# 03_RS485.net
KiCad netlist of a schematic drawn in Altium Designer
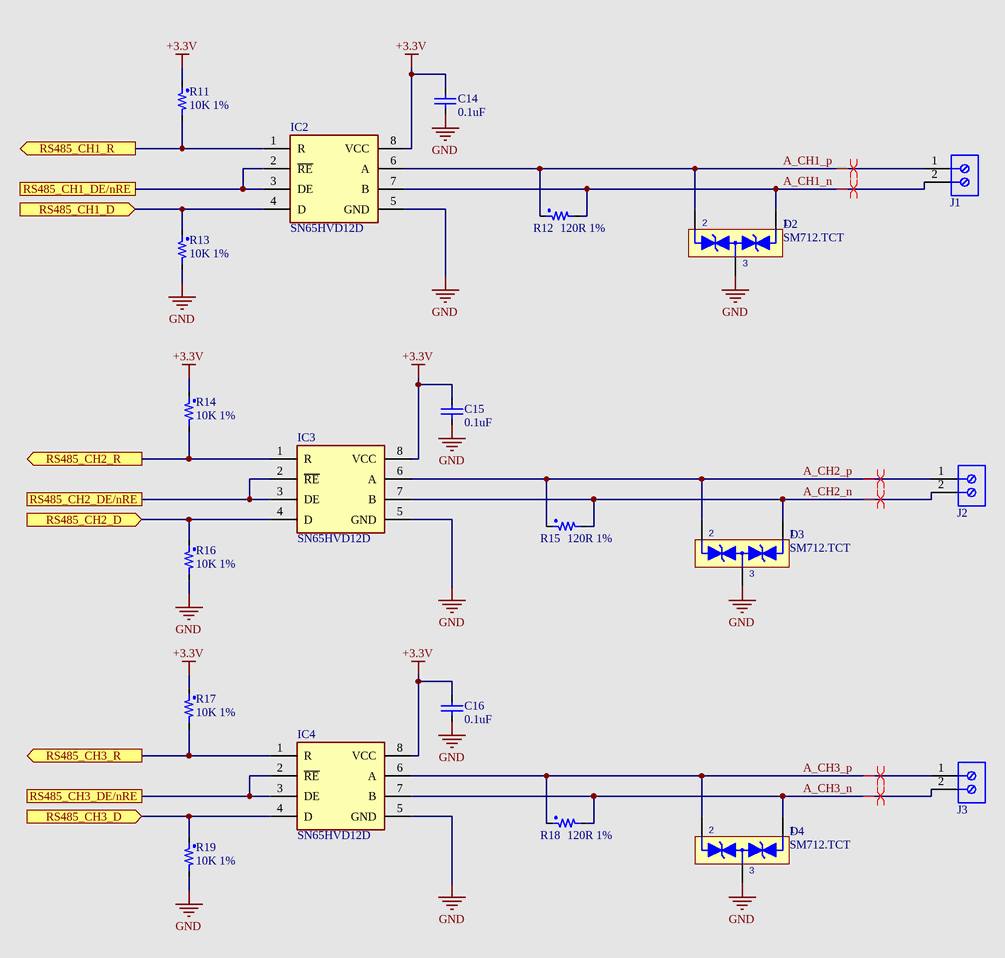
[diagram p0: 03_RS485.SchDoc]

(export (version "E")
  (design (tool "Eeschema 10.0.6"))
  (components
    (comp (ref "C14")
      (value "0.1uF")
      (footprint "Capacitor:C0603 (1608 metric)")
      (description "Multilayer Ceramic Capacitors MLCC - SMD/SMT 0.1uF 50V X7R +/-10% 0603")
      (fields (field (name "MFR PART NUMBER") "CC0603KRX7R9BB104") (field (name "MFR") "Yageo"))
      (libsource (lib "CeramicCapacitor") (part "CC0603KRX7R9BB104"))
    )
    (comp (ref "C15")
      (value "0.1uF")
      (footprint "Capacitor:C0603 (1608 metric)")
      (description "Multilayer Ceramic Capacitors MLCC - SMD/SMT 0.1uF 50V X7R +/-10% 0603")
      (fields (field (name "MFR PART NUMBER") "CC0603KRX7R9BB104") (field (name "MFR") "Yageo"))
      (libsource (lib "CeramicCapacitor") (part "CC0603KRX7R9BB104"))
    )
    (comp (ref "C16")
      (value "0.1uF")
      (footprint "Capacitor:C0603 (1608 metric)")
      (description "Multilayer Ceramic Capacitors MLCC - SMD/SMT 0.1uF 50V X7R +/-10% 0603")
      (fields (field (name "MFR PART NUMBER") "CC0603KRX7R9BB104") (field (name "MFR") "Yageo"))
      (libsource (lib "CeramicCapacitor") (part "CC0603KRX7R9BB104"))
    )
    (comp (ref "D2")
      (value "SM712.TCT")
      (footprint "SM712")
      (description "ESD Suppressors / TVS Diodes 400W ASYMMETRICAL TVS 7V,12V")
      (fields (field (name "MFR") "SEMTECH"))
      (libsource (lib "ESD Suppressors and TVS Diodes") (part "SM712.TCT"))
    )
    (comp (ref "D3")
      (value "SM712.TCT")
      (footprint "SM712")
      (description "ESD Suppressors / TVS Diodes 400W ASYMMETRICAL TVS 7V,12V")
      (fields (field (name "MFR") "SEMTECH"))
      (libsource (lib "ESD Suppressors and TVS Diodes") (part "SM712.TCT"))
    )
    (comp (ref "D4")
      (value "SM712.TCT")
      (footprint "SM712")
      (description "ESD Suppressors / TVS Diodes 400W ASYMMETRICAL TVS 7V,12V")
      (fields (field (name "MFR") "SEMTECH"))
      (libsource (lib "ESD Suppressors and TVS Diodes") (part "SM712.TCT"))
    )
    (comp (ref "IC2")
      (value "SN65HVD12D")
      (footprint "SOIC8")
      (description "RS-485 Interface IC 3.3V Differential Transceivers")
      (fields (field (name "MFR") "Texas Instruments") (field (name "MFR PART NUMBER") "SN65HVD12DR"))
      (libsource (lib "Interface") (part "SN65HVD12D"))
    )
    (comp (ref "IC3")
      (value "SN65HVD12D")
      (footprint "SOIC8")
      (description "RS-485 Interface IC 3.3V Differential Transceivers")
      (fields (field (name "MFR") "Texas Instruments") (field (name "MFR PART NUMBER") "SN65HVD12DR"))
      (libsource (lib "Interface") (part "SN65HVD12D"))
    )
    (comp (ref "IC4")
      (value "SN65HVD12D")
      (footprint "SOIC8")
      (description "RS-485 Interface IC 3.3V Differential Transceivers")
      (fields (field (name "MFR") "Texas Instruments") (field (name "MFR PART NUMBER") "SN65HVD12DR"))
      (libsource (lib "Interface") (part "SN65HVD12D"))
    )
    (comp (ref "J1")
      (value "691103110002")
      (footprint "691103110002")
      (description "WR-TBL Series 1031 Horizontal Entry Modular, THT, pitch 3.5mm, 2p")
      (fields (field (name "MFR") "Wurth Elektronik"))
      (libsource (lib "Altium_WR-TBL (rev22b)") (part "691103110002"))
    )
    (comp (ref "J2")
      (value "691103110002")
      (footprint "691103110002")
      (description "WR-TBL Series 1031 Horizontal Entry Modular, THT, pitch 3.5mm, 2p")
      (fields (field (name "MFR") "Wurth Elektronik"))
      (libsource (lib "Altium_WR-TBL (rev22b)") (part "691103110002"))
    )
    (comp (ref "J3")
      (value "691103110002")
      (footprint "691103110002")
      (description "WR-TBL Series 1031 Horizontal Entry Modular, THT, pitch 3.5mm, 2p")
      (fields (field (name "MFR") "Wurth Elektronik"))
      (libsource (lib "Altium_WR-TBL (rev22b)") (part "691103110002"))
    )
    (comp (ref "R11")
      (value "10K 1%")
      (footprint "Resistor:R0603 (1608 Metric)")
      (description "Thick Film Resistors - SMD 10K OHM 1% Case 0603")
      (fields (field (name "MFR PART NUMBER") "RC0603FR-0710KL") (field (name "MFR") "Yageo"))
      (libsource (lib "ChipResistor") (part "RC0603FR-0710KL"))
    )
    (comp (ref "R12")
      (value "120R 1%")
      (footprint "Resistor:R0805 (2012 METRIC)")
      (description "Thick Film Resistors - SMD 120 OHM 1%")
      (fields (field (name "MFR PART NUMBER") "RC0805FR-07120RL") (field (name "MFR") "Yageo"))
      (libsource (lib "ChipResistor") (part "RC0805FR-07120RL"))
    )
    (comp (ref "R13")
      (value "10K 1%")
      (footprint "Resistor:R0603 (1608 Metric)")
      (description "Thick Film Resistors - SMD 10K OHM 1% Case 0603")
      (fields (field (name "MFR PART NUMBER") "RC0603FR-0710KL") (field (name "MFR") "Yageo"))
      (libsource (lib "ChipResistor") (part "RC0603FR-0710KL"))
    )
    (comp (ref "R14")
      (value "10K 1%")
      (footprint "Resistor:R0603 (1608 Metric)")
      (description "Thick Film Resistors - SMD 10K OHM 1% Case 0603")
      (fields (field (name "MFR PART NUMBER") "RC0603FR-0710KL") (field (name "MFR") "Yageo"))
      (libsource (lib "ChipResistor") (part "RC0603FR-0710KL"))
    )
    (comp (ref "R15")
      (value "120R 1%")
      (footprint "Resistor:R0805 (2012 METRIC)")
      (description "Thick Film Resistors - SMD 120 OHM 1%")
      (fields (field (name "MFR PART NUMBER") "RC0805FR-07120RL") (field (name "MFR") "Yageo"))
      (libsource (lib "ChipResistor") (part "RC0805FR-07120RL"))
    )
    (comp (ref "R16")
      (value "10K 1%")
      (footprint "Resistor:R0603 (1608 Metric)")
      (description "Thick Film Resistors - SMD 10K OHM 1% Case 0603")
      (fields (field (name "MFR PART NUMBER") "RC0603FR-0710KL") (field (name "MFR") "Yageo"))
      (libsource (lib "ChipResistor") (part "RC0603FR-0710KL"))
    )
    (comp (ref "R17")
      (value "10K 1%")
      (footprint "Resistor:R0603 (1608 Metric)")
      (description "Thick Film Resistors - SMD 10K OHM 1% Case 0603")
      (fields (field (name "MFR PART NUMBER") "RC0603FR-0710KL") (field (name "MFR") "Yageo"))
      (libsource (lib "ChipResistor") (part "RC0603FR-0710KL"))
    )
    (comp (ref "R18")
      (value "120R 1%")
      (footprint "Resistor:R0805 (2012 METRIC)")
      (description "Thick Film Resistors - SMD 120 OHM 1%")
      (fields (field (name "MFR PART NUMBER") "RC0805FR-07120RL") (field (name "MFR") "Yageo"))
      (libsource (lib "ChipResistor") (part "RC0805FR-07120RL"))
    )
    (comp (ref "R19")
      (value "10K 1%")
      (footprint "Resistor:R0603 (1608 Metric)")
      (description "Thick Film Resistors - SMD 10K OHM 1% Case 0603")
      (fields (field (name "MFR PART NUMBER") "RC0603FR-0710KL") (field (name "MFR") "Yageo"))
      (libsource (lib "ChipResistor") (part "RC0603FR-0710KL"))
    )
  )
  (nets
    (net (code "1") (name "+3.3V") (class "Default")
      (node (ref "C14") (pin "1") (pinfunction "1_1") (pintype "passive"))
      (node (ref "C15") (pin "1") (pinfunction "1_1") (pintype "passive"))
      (node (ref "C16") (pin "1") (pinfunction "1_1") (pintype "passive"))
      (node (ref "IC2") (pin "8") (pinfunction "VCC_8") (pintype "passive"))
      (node (ref "IC3") (pin "8") (pinfunction "VCC_8") (pintype "passive"))
      (node (ref "IC4") (pin "8") (pinfunction "VCC_8") (pintype "passive"))
      (node (ref "R11") (pin "1") (pinfunction "1_1") (pintype "passive"))
      (node (ref "R14") (pin "1") (pinfunction "1_1") (pintype "passive"))
      (node (ref "R17") (pin "1") (pinfunction "1_1") (pintype "passive"))
    )
    (net (code "2") (name "/A_CH1_n") (class "Default")
      (node (ref "D2") (pin "1") (pinfunction "I/O1_1") (pintype "passive"))
      (node (ref "IC2") (pin "7") (pinfunction "B_7") (pintype "passive"))
      (node (ref "J1") (pin "2") (pinfunction "2_2") (pintype "passive"))
      (node (ref "R12") (pin "2") (pinfunction "2_2") (pintype "passive"))
    )
    (net (code "3") (name "/A_CH1_p") (class "Default")
      (node (ref "D2") (pin "2") (pinfunction "I/O2_2") (pintype "passive"))
      (node (ref "IC2") (pin "6") (pinfunction "A_6") (pintype "passive"))
      (node (ref "J1") (pin "1") (pinfunction "1_1") (pintype "passive"))
      (node (ref "R12") (pin "1") (pinfunction "1_1") (pintype "passive"))
    )
    (net (code "4") (name "/A_CH2_n") (class "Default")
      (node (ref "D3") (pin "1") (pinfunction "I/O1_1") (pintype "passive"))
      (node (ref "IC3") (pin "7") (pinfunction "B_7") (pintype "passive"))
      (node (ref "J2") (pin "2") (pinfunction "2_2") (pintype "passive"))
      (node (ref "R15") (pin "2") (pinfunction "2_2") (pintype "passive"))
    )
    (net (code "5") (name "/A_CH2_p") (class "Default")
      (node (ref "D3") (pin "2") (pinfunction "I/O2_2") (pintype "passive"))
      (node (ref "IC3") (pin "6") (pinfunction "A_6") (pintype "passive"))
      (node (ref "J2") (pin "1") (pinfunction "1_1") (pintype "passive"))
      (node (ref "R15") (pin "1") (pinfunction "1_1") (pintype "passive"))
    )
    (net (code "6") (name "/A_CH3_n") (class "Default")
      (node (ref "D4") (pin "1") (pinfunction "I/O1_1") (pintype "passive"))
      (node (ref "IC4") (pin "7") (pinfunction "B_7") (pintype "passive"))
      (node (ref "J3") (pin "2") (pinfunction "2_2") (pintype "passive"))
      (node (ref "R18") (pin "2") (pinfunction "2_2") (pintype "passive"))
    )
    (net (code "7") (name "/A_CH3_p") (class "Default")
      (node (ref "D4") (pin "2") (pinfunction "I/O2_2") (pintype "passive"))
      (node (ref "IC4") (pin "6") (pinfunction "A_6") (pintype "passive"))
      (node (ref "J3") (pin "1") (pinfunction "1_1") (pintype "passive"))
      (node (ref "R18") (pin "1") (pinfunction "1_1") (pintype "passive"))
    )
    (net (code "8") (name "/RS485_CH1_D") (class "Default")
      (node (ref "IC2") (pin "4") (pinfunction "D_4") (pintype "passive"))
      (node (ref "R13") (pin "1") (pinfunction "1_1") (pintype "passive"))
    )
    (net (code "9") (name "/RS485_CH1_DE{slash}nRE") (class "Default")
      (node (ref "IC2") (pin "2") (pinfunction "~{RE}_2") (pintype "passive"))
      (node (ref "IC2") (pin "3") (pinfunction "DE_3") (pintype "passive"))
    )
    (net (code "10") (name "/RS485_CH1_R") (class "Default")
      (node (ref "IC2") (pin "1") (pinfunction "R_1") (pintype "passive"))
      (node (ref "R11") (pin "2") (pinfunction "2_2") (pintype "passive"))
    )
    (net (code "11") (name "/RS485_CH2_D") (class "Default")
      (node (ref "IC3") (pin "4") (pinfunction "D_4") (pintype "passive"))
      (node (ref "R16") (pin "1") (pinfunction "1_1") (pintype "passive"))
    )
    (net (code "12") (name "/RS485_CH2_DE{slash}nRE") (class "Default")
      (node (ref "IC3") (pin "2") (pinfunction "~{RE}_2") (pintype "passive"))
      (node (ref "IC3") (pin "3") (pinfunction "DE_3") (pintype "passive"))
    )
    (net (code "13") (name "/RS485_CH2_R") (class "Default")
      (node (ref "IC3") (pin "1") (pinfunction "R_1") (pintype "passive"))
      (node (ref "R14") (pin "2") (pinfunction "2_2") (pintype "passive"))
    )
    (net (code "14") (name "/RS485_CH3_D") (class "Default")
      (node (ref "IC4") (pin "4") (pinfunction "D_4") (pintype "passive"))
      (node (ref "R19") (pin "1") (pinfunction "1_1") (pintype "passive"))
    )
    (net (code "15") (name "/RS485_CH3_DE{slash}nRE") (class "Default")
      (node (ref "IC4") (pin "2") (pinfunction "~{RE}_2") (pintype "passive"))
      (node (ref "IC4") (pin "3") (pinfunction "DE_3") (pintype "passive"))
    )
    (net (code "16") (name "/RS485_CH3_R") (class "Default")
      (node (ref "IC4") (pin "1") (pinfunction "R_1") (pintype "passive"))
      (node (ref "R17") (pin "2") (pinfunction "2_2") (pintype "passive"))
    )
    (net (code "17") (name "GND") (class "Default")
      (node (ref "C14") (pin "2") (pinfunction "2_2") (pintype "passive"))
      (node (ref "C15") (pin "2") (pinfunction "2_2") (pintype "passive"))
      (node (ref "C16") (pin "2") (pinfunction "2_2") (pintype "passive"))
      (node (ref "D2") (pin "3") (pinfunction "GND_3") (pintype "passive"))
      (node (ref "D3") (pin "3") (pinfunction "GND_3") (pintype "passive"))
      (node (ref "D4") (pin "3") (pinfunction "GND_3") (pintype "passive"))
      (node (ref "IC2") (pin "5") (pinfunction "GND_5") (pintype "passive"))
      (node (ref "IC3") (pin "5") (pinfunction "GND_5") (pintype "passive"))
      (node (ref "IC4") (pin "5") (pinfunction "GND_5") (pintype "passive"))
      (node (ref "R13") (pin "2") (pinfunction "2_2") (pintype "passive"))
      (node (ref "R16") (pin "2") (pinfunction "2_2") (pintype "passive"))
      (node (ref "R19") (pin "2") (pinfunction "2_2") (pintype "passive"))
    )
  )
)
